# PIC12F629.net
KiCad netlist of a schematic drawn in EAGLE
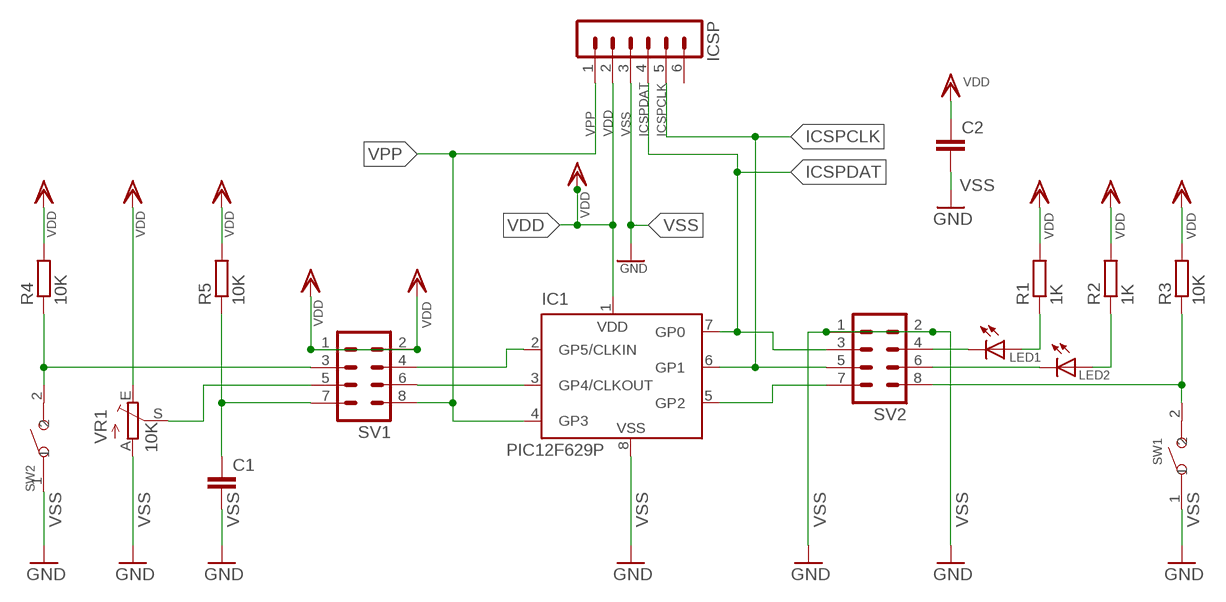
[diagram p0: schematic, sheet 1]

(export (version "E")
  (design (tool "Eeschema 10.0.6"))
  (components
    (comp (ref "C1")
      (value "C-EUC0805K")
      (footprint "eagle-import:C0805K")
      (libsource (lib "eagle-import") (part "C-EUC0805K"))
    )
    (comp (ref "C2")
      (value "C-EUC0805K")
      (footprint "eagle-import:C0805K")
      (libsource (lib "eagle-import") (part "C-EUC0805K"))
    )
    (comp (ref "IC1")
      (value "PIC12F629P")
      (footprint "eagle-import:DIL8")
      (fields (field (name "MF") "MICROCHIP") (field (name "MPN") "PIC12F629-I/P"))
      (libsource (lib "eagle-import") (part "PIC12F6P29"))
    )
    (comp (ref "ICSP")
      (value "MA06-1")
      (footprint "eagle-import:MA06-1")
      (libsource (lib "eagle-import") (part "MA06-1"))
    )
    (comp (ref "LED1")
      (value "LEDCHIP-LED0805")
      (footprint "eagle-import:CHIP-LED0805")
      (libsource (lib "eagle-import") (part "LEDCHIP-LED0805"))
    )
    (comp (ref "LED2")
      (value "LEDCHIP-LED0805")
      (footprint "eagle-import:CHIP-LED0805")
      (libsource (lib "eagle-import") (part "LEDCHIP-LED0805"))
    )
    (comp (ref "R1")
      (value "1K")
      (footprint "eagle-import:R0805")
      (libsource (lib "eagle-import") (part "R-EU_R0805"))
    )
    (comp (ref "R2")
      (value "1K")
      (footprint "eagle-import:R0805")
      (libsource (lib "eagle-import") (part "R-EU_R0805"))
    )
    (comp (ref "R3")
      (value "10K")
      (footprint "eagle-import:R0805")
      (libsource (lib "eagle-import") (part "R-EU_R0805"))
    )
    (comp (ref "R4")
      (value "10K")
      (footprint "eagle-import:R0805")
      (libsource (lib "eagle-import") (part "R-EU_R0805"))
    )
    (comp (ref "R5")
      (value "10K")
      (footprint "eagle-import:R0805")
      (libsource (lib "eagle-import") (part "R-EU_R0805"))
    )
    (comp (ref "SV1")
      (value "MA04-2")
      (footprint "eagle-import:MA04-2")
      (libsource (lib "eagle-import") (part "MA04-2"))
    )
    (comp (ref "SV2")
      (value "MA04-2")
      (footprint "eagle-import:MA04-2")
      (libsource (lib "eagle-import") (part "MA04-2"))
    )
    (comp (ref "SW1")
      (value "SMD-BUTTON(2P-6.0X3.0X2.5MM)-DHT-1163S")
      (footprint "eagle-import:SW2-4.0-6.0X3.0X2.5MM")
      (libsource (lib "eagle-import") (part "SMD-BUTTON(2P-6.0X3.0X2.5MM)-DHT-1163S"))
    )
    (comp (ref "SW2")
      (value "SMD-BUTTON(2P-6.0X3.0X2.5MM)-DHT-1163S")
      (footprint "eagle-import:SW2-4.0-6.0X3.0X2.5MM")
      (libsource (lib "eagle-import") (part "SMD-BUTTON(2P-6.0X3.0X2.5MM)-DHT-1163S"))
    )
    (comp (ref "VR1")
      (value "10K")
      (footprint "eagle-import:CA6V")
      (libsource (lib "eagle-import") (part "TRIM_EU-CA6V"))
    )
  )
  (nets
    (net (code "1") (name "ICSPCLK") (class "Default")
      (node (ref "IC1") (pin "6") (pinfunction "GP1_6") (pintype "bidirectional"))
      (node (ref "ICSP") (pin "5") (pinfunction "5_5") (pintype "passive"))
      (node (ref "SV2") (pin "5") (pinfunction "5_5") (pintype "passive"))
    )
    (net (code "2") (name "ICSPDAT") (class "Default")
      (node (ref "IC1") (pin "7") (pinfunction "GP0_7") (pintype "bidirectional"))
      (node (ref "ICSP") (pin "4") (pinfunction "4_4") (pintype "passive"))
      (node (ref "SV2") (pin "3") (pinfunction "3_3") (pintype "passive"))
    )
    (net (code "3") (name "Net-(C1-Pad1)") (class "Default")
      (node (ref "C1") (pin "1") (pinfunction "1_1") (pintype "passive"))
      (node (ref "R5") (pin "1") (pinfunction "1_1") (pintype "passive"))
      (node (ref "SV1") (pin "7") (pinfunction "7_7") (pintype "passive"))
    )
    (net (code "4") (name "Net-(IC1-GP2)") (class "Default")
      (node (ref "IC1") (pin "5") (pinfunction "GP2_5") (pintype "bidirectional"))
      (node (ref "SV2") (pin "7") (pinfunction "7_7") (pintype "passive"))
    )
    (net (code "5") (name "Net-(IC1-GP4{slash}CLKOUT)") (class "Default")
      (node (ref "IC1") (pin "3") (pinfunction "GP4/CLKOUT_3") (pintype "bidirectional"))
      (node (ref "SV1") (pin "6") (pinfunction "6_6") (pintype "passive"))
    )
    (net (code "6") (name "Net-(IC1-GP5{slash}CLKIN)") (class "Default")
      (node (ref "IC1") (pin "2") (pinfunction "GP5/CLKIN_2") (pintype "bidirectional"))
      (node (ref "SV1") (pin "4") (pinfunction "4_4") (pintype "passive"))
    )
    (net (code "7") (name "Net-(LED1-PadA)") (class "Default")
      (node (ref "LED1") (pin "A") (pinfunction "A_A") (pintype "passive"))
      (node (ref "R1") (pin "1") (pinfunction "1_1") (pintype "passive"))
    )
    (net (code "8") (name "Net-(LED1-PadC)") (class "Default")
      (node (ref "LED1") (pin "C") (pinfunction "C_C") (pintype "passive"))
      (node (ref "SV2") (pin "4") (pinfunction "4_4") (pintype "passive"))
    )
    (net (code "9") (name "Net-(LED2-PadA)") (class "Default")
      (node (ref "LED2") (pin "A") (pinfunction "A_A") (pintype "passive"))
      (node (ref "R2") (pin "1") (pinfunction "1_1") (pintype "passive"))
    )
    (net (code "10") (name "Net-(LED2-PadC)") (class "Default")
      (node (ref "LED2") (pin "C") (pinfunction "C_C") (pintype "passive"))
      (node (ref "SV2") (pin "6") (pinfunction "6_6") (pintype "passive"))
    )
    (net (code "11") (name "Net-(R3-Pad1)") (class "Default")
      (node (ref "R3") (pin "1") (pinfunction "1_1") (pintype "passive"))
      (node (ref "SV2") (pin "8") (pinfunction "8_8") (pintype "passive"))
      (node (ref "SW1") (pin "2") (pinfunction "2_2") (pintype "bidirectional"))
    )
    (net (code "12") (name "Net-(R4-Pad1)") (class "Default")
      (node (ref "R4") (pin "1") (pinfunction "1_1") (pintype "passive"))
      (node (ref "SV1") (pin "3") (pinfunction "3_3") (pintype "passive"))
      (node (ref "SW2") (pin "2") (pinfunction "2_2") (pintype "bidirectional"))
    )
    (net (code "13") (name "Net-(SV1-Pad5)") (class "Default")
      (node (ref "SV1") (pin "5") (pinfunction "5_5") (pintype "passive"))
      (node (ref "VR1") (pin "S") (pinfunction "S_S") (pintype "passive"))
    )
    (net (code "14") (name "VDD") (class "Default")
      (node (ref "C2") (pin "1") (pinfunction "1_1") (pintype "passive"))
      (node (ref "IC1") (pin "1") (pinfunction "VDD_1") (pintype "power_in"))
      (node (ref "ICSP") (pin "2") (pinfunction "2_2") (pintype "passive"))
      (node (ref "R1") (pin "2") (pinfunction "2_2") (pintype "passive"))
      (node (ref "R2") (pin "2") (pinfunction "2_2") (pintype "passive"))
      (node (ref "R3") (pin "2") (pinfunction "2_2") (pintype "passive"))
      (node (ref "R4") (pin "2") (pinfunction "2_2") (pintype "passive"))
      (node (ref "R5") (pin "2") (pinfunction "2_2") (pintype "passive"))
      (node (ref "SV1") (pin "1") (pinfunction "1_1") (pintype "passive"))
      (node (ref "SV1") (pin "2") (pinfunction "2_2") (pintype "passive"))
      (node (ref "VR1") (pin "E") (pinfunction "E_E") (pintype "passive"))
    )
    (net (code "15") (name "VPP") (class "Default")
      (node (ref "IC1") (pin "4") (pinfunction "GP3_4") (pintype "input"))
      (node (ref "ICSP") (pin "1") (pinfunction "1_1") (pintype "passive"))
      (node (ref "SV1") (pin "8") (pinfunction "8_8") (pintype "passive"))
    )
    (net (code "16") (name "VSS") (class "Default")
      (node (ref "C1") (pin "2") (pinfunction "2_2") (pintype "passive"))
      (node (ref "C2") (pin "2") (pinfunction "2_2") (pintype "passive"))
      (node (ref "IC1") (pin "8") (pinfunction "VSS_8") (pintype "power_in"))
      (node (ref "ICSP") (pin "3") (pinfunction "3_3") (pintype "passive"))
      (node (ref "SV2") (pin "1") (pinfunction "1_1") (pintype "passive"))
      (node (ref "SV2") (pin "2") (pinfunction "2_2") (pintype "passive"))
      (node (ref "SW1") (pin "1") (pinfunction "1_1") (pintype "bidirectional"))
      (node (ref "SW2") (pin "1") (pinfunction "1_1") (pintype "bidirectional"))
      (node (ref "VR1") (pin "A") (pinfunction "A_A") (pintype "passive"))
    )
    (net (code "17") (name "unconnected-(ICSP-Pad6)") (class "Default")
      (node (ref "ICSP") (pin "6") (pinfunction "6_6") (pintype "passive"))
    )
  )
)
